# Embedded_Circuits.net
KiCad netlist of a schematic drawn in Altium Designer
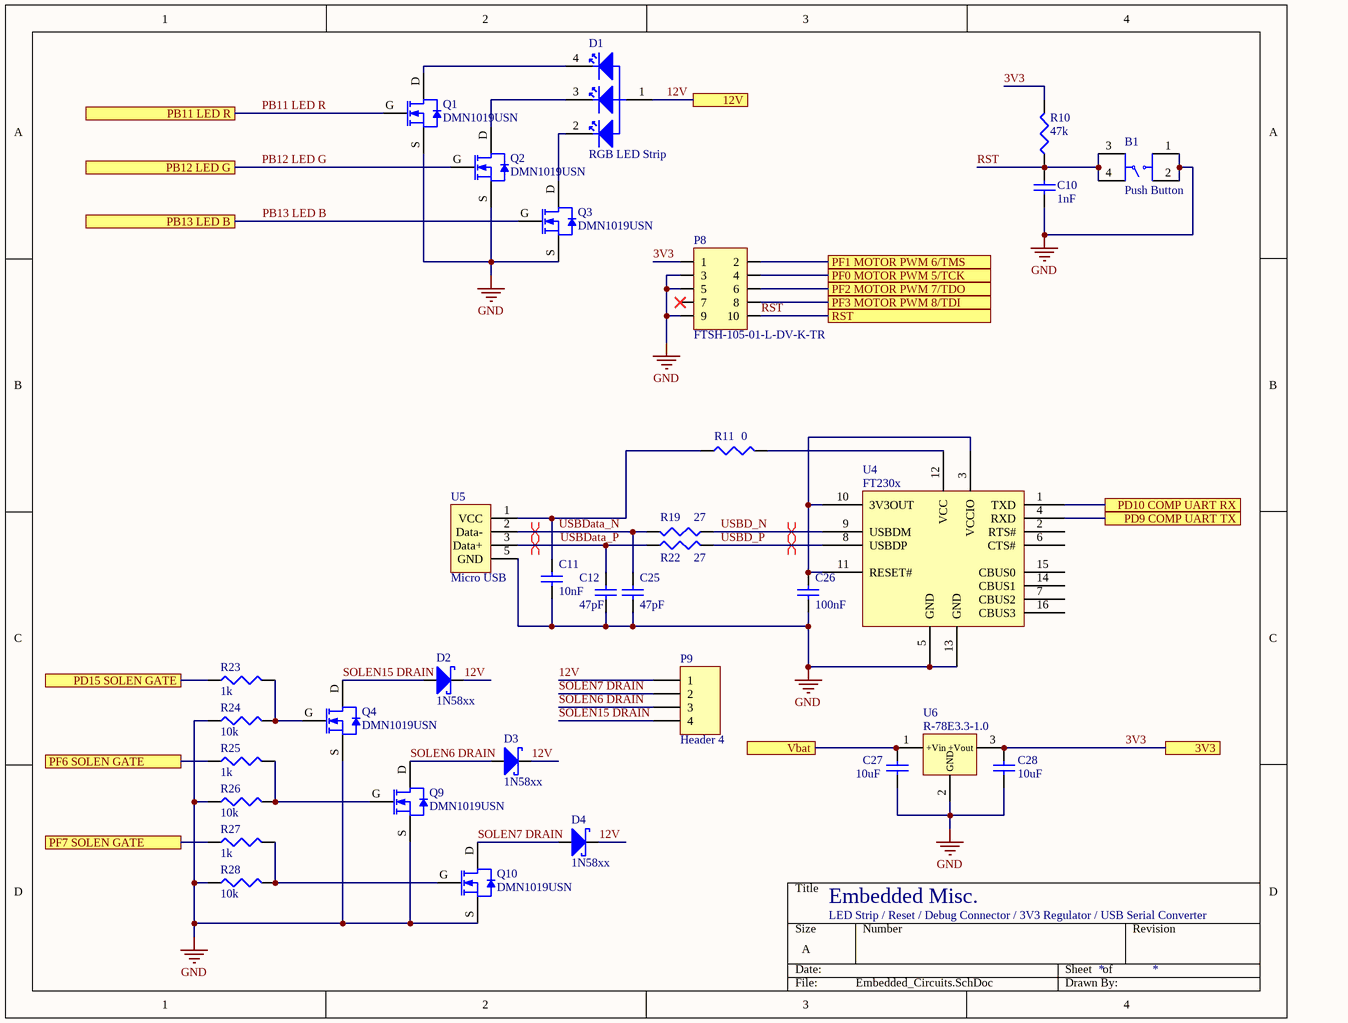
[diagram p0: Embedded_Circuits.SchDoc]

(export (version "E")
  (design (tool "Eeschema 10.0.6"))
  (components
    (comp (ref "B1")
      (value "Push Button")
      (footprint "Push Button")
      (description "Tactile Switch SPST-NO Top Actuated Through Hole")
      (libsource (lib "Power_Embedded_Board_Library") (part "Push Button"))
    )
    (comp (ref "C10")
      (value "1nF")
      (footprint "C1206")
      (description "Capacitor (Semiconductor SIM Model)")
      (fields (field (name "Comment") "Cap Semi") (field (name "PUBLISHER") "Altium Limited"))
      (libsource (lib "Miscellaneous Devices") (part "Cap Semi"))
    )
    (comp (ref "C11")
      (value "10nF")
      (footprint "C1206")
      (description "Capacitor")
      (fields (field (name "Comment") "Cap") (field (name "PUBLISHER") "Altium Limited"))
      (libsource (lib "Miscellaneous Devices") (part "Cap"))
    )
    (comp (ref "C12")
      (value "47pF")
      (footprint "C1206")
      (description "Capacitor")
      (fields (field (name "Comment") "Cap") (field (name "PUBLISHER") "Altium Limited"))
      (libsource (lib "Miscellaneous Devices") (part "Cap"))
    )
    (comp (ref "C25")
      (value "47pF")
      (footprint "C1206")
      (description "Capacitor")
      (fields (field (name "Comment") "Cap") (field (name "PUBLISHER") "Altium Limited"))
      (libsource (lib "Miscellaneous Devices") (part "Cap"))
    )
    (comp (ref "C26")
      (value "100nF")
      (footprint "C1206")
      (description "Capacitor")
      (fields (field (name "Comment") "Cap") (field (name "PUBLISHER") "Altium Limited"))
      (libsource (lib "Miscellaneous Devices") (part "Cap"))
    )
    (comp (ref "C27")
      (value "10uF")
      (footprint "C1206")
      (description "Capacitor")
      (fields (field (name "Comment") "Cap") (field (name "PUBLISHER") "Altium Limited"))
      (libsource (lib "Miscellaneous Devices") (part "Cap"))
    )
    (comp (ref "C28")
      (value "10uF")
      (footprint "C1206")
      (description "Capacitor")
      (fields (field (name "Comment") "Cap") (field (name "PUBLISHER") "Altium Limited"))
      (libsource (lib "Miscellaneous Devices") (part "Cap"))
    )
    (comp (ref "D1")
      (value "RGB LED Strip")
      (footprint "Header 1x4")
      (description "LED RGB Strip - Bare Nonaddressable")
      (libsource (lib "Power_Embedded_Board_Library") (part "RGB LED Strip"))
    )
    (comp (ref "D2")
      (value "1N58xx")
      (footprint "1N58xx")
      (description "1A Schottky Barrier Rectifier Diode")
      (libsource (lib "Power_Embedded_Board_Library") (part "1N58xx"))
    )
    (comp (ref "D3")
      (value "1N58xx")
      (footprint "1N58xx")
      (description "1A Schottky Barrier Rectifier Diode")
      (libsource (lib "Power_Embedded_Board_Library") (part "1N58xx"))
    )
    (comp (ref "D4")
      (value "1N58xx")
      (footprint "1N58xx")
      (description "1A Schottky Barrier Rectifier Diode")
      (libsource (lib "Power_Embedded_Board_Library") (part "1N58xx"))
    )
    (comp (ref "P8")
      (value "FTSH-105-01-L-DV-K-TR")
      (footprint "FTSH-105-01-L-DV-K-TR")
      (description "CONN HEADER 10POS DUAL .05\" SMD")
      (libsource (lib "Power_Embedded_Board_Library") (part "JTAG Header"))
    )
    (comp (ref "P9")
      (value "Header 4")
      (footprint "Header 1x4")
      (description "Header, 4-Pin")
      (fields (field (name "PUBLISHER") "Altium Limited"))
      (libsource (lib "Miscellaneous Connectors") (part "Header 4"))
    )
    (comp (ref "Q1")
      (value "DMN1019USN")
      (footprint "SOT-23")
      (description "12V N-Channel Enhancement Mode MOSFET")
      (libsource (lib "Power_Embedded_Board_Library") (part "DMN1019USN"))
    )
    (comp (ref "Q2")
      (value "DMN1019USN")
      (footprint "SOT-23")
      (description "12V N-Channel Enhancement Mode MOSFET")
      (libsource (lib "Power_Embedded_Board_Library") (part "DMN1019USN"))
    )
    (comp (ref "Q3")
      (value "DMN1019USN")
      (footprint "SOT-23")
      (description "12V N-Channel Enhancement Mode MOSFET")
      (libsource (lib "Power_Embedded_Board_Library") (part "DMN1019USN"))
    )
    (comp (ref "Q4")
      (value "DMN1019USN")
      (footprint "SOT-23")
      (description "12V N-Channel Enhancement Mode MOSFET")
      (libsource (lib "Power_Embedded_Board_Library") (part "DMN1019USN"))
    )
    (comp (ref "Q9")
      (value "DMN1019USN")
      (footprint "SOT-23")
      (description "12V N-Channel Enhancement Mode MOSFET")
      (libsource (lib "Power_Embedded_Board_Library") (part "DMN1019USN"))
    )
    (comp (ref "Q10")
      (value "DMN1019USN")
      (footprint "SOT-23")
      (description "12V N-Channel Enhancement Mode MOSFET")
      (libsource (lib "Power_Embedded_Board_Library") (part "DMN1019USN"))
    )
    (comp (ref "R10")
      (value "47k")
      (footprint "J1-0603")
      (description "Resistor")
      (fields (field (name "Comment") "Res3") (field (name "PUBLISHER") "Altium Limited"))
      (libsource (lib "Miscellaneous Devices") (part "Res3"))
    )
    (comp (ref "R11")
      (value "0")
      (footprint "J1-0603")
      (description "Resistor")
      (fields (field (name "Comment") "Res3") (field (name "PUBLISHER") "Altium Limited"))
      (libsource (lib "Miscellaneous Devices") (part "Res3"))
    )
    (comp (ref "R19")
      (value "27")
      (footprint "J1-0603")
      (description "Resistor")
      (fields (field (name "Comment") "Res3") (field (name "PUBLISHER") "Altium Limited"))
      (libsource (lib "Miscellaneous Devices") (part "Res3"))
    )
    (comp (ref "R22")
      (value "27")
      (footprint "J1-0603")
      (description "Resistor")
      (fields (field (name "Comment") "Res3") (field (name "PUBLISHER") "Altium Limited"))
      (libsource (lib "Miscellaneous Devices") (part "Res3"))
    )
    (comp (ref "R23")
      (value "1k")
      (footprint "J1-0603")
      (description "Resistor")
      (fields (field (name "Comment") "Res3") (field (name "PUBLISHER") "Altium Limited"))
      (libsource (lib "Miscellaneous Devices") (part "Res3"))
    )
    (comp (ref "R24")
      (value "10k")
      (footprint "J1-0603")
      (description "Resistor")
      (fields (field (name "Comment") "Res3") (field (name "PUBLISHER") "Altium Limited"))
      (libsource (lib "Miscellaneous Devices") (part "Res3"))
    )
    (comp (ref "R25")
      (value "1k")
      (footprint "J1-0603")
      (description "Resistor")
      (fields (field (name "Comment") "Res3") (field (name "PUBLISHER") "Altium Limited"))
      (libsource (lib "Miscellaneous Devices") (part "Res3"))
    )
    (comp (ref "R26")
      (value "10k")
      (footprint "J1-0603")
      (description "Resistor")
      (fields (field (name "Comment") "Res3") (field (name "PUBLISHER") "Altium Limited"))
      (libsource (lib "Miscellaneous Devices") (part "Res3"))
    )
    (comp (ref "R27")
      (value "1k")
      (footprint "J1-0603")
      (description "Resistor")
      (fields (field (name "Comment") "Res3") (field (name "PUBLISHER") "Altium Limited"))
      (libsource (lib "Miscellaneous Devices") (part "Res3"))
    )
    (comp (ref "R28")
      (value "10k")
      (footprint "J1-0603")
      (description "Resistor")
      (fields (field (name "Comment") "Res3") (field (name "PUBLISHER") "Altium Limited"))
      (libsource (lib "Miscellaneous Devices") (part "Res3"))
    )
    (comp (ref "U4")
      (value "FT230x")
      (footprint "FT230X")
      (description "USB to Basic UART IC")
      (libsource (lib "Power_Embedded_Board_Library") (part "FTDI FT230x"))
    )
    (comp (ref "U5")
      (value "Micro USB")
      (footprint "Micro USB")
      (description "USB - micro B USB 2.0 Receptacle Connector 5 Position Surface Mount, Right Angle")
      (libsource (lib "Power_Embedded_Board_Library") (part "Micro USB"))
    )
    (comp (ref "U6")
      (value "R-78E3.3-1.0")
      (footprint "R-78Exx-1.0")
      (description "1A DC/DC Voltage Converter")
      (libsource (lib "Power_Embedded_Board_Library") (part "R-78Exx-1.0"))
    )
  )
  (nets
    (net (code "1") (name "/3V3") (class "Default")
      (node (ref "C28") (pin "2") (pinfunction "2_2") (pintype "passive"))
      (node (ref "P8") (pin "1") (pinfunction "1_1") (pintype "passive"))
      (node (ref "R10") (pin "2") (pinfunction "2_2") (pintype "passive"))
      (node (ref "U6") (pin "3") (pinfunction "+Vout_3") (pintype "passive"))
    )
    (net (code "2") (name "/12V") (class "Default")
      (node (ref "D1") (pin "1") (pinfunction "1_1") (pintype "passive"))
      (node (ref "D2") (pin "K") (pinfunction "Cathode_K") (pintype "passive"))
      (node (ref "D3") (pin "K") (pinfunction "Cathode_K") (pintype "passive"))
      (node (ref "D4") (pin "K") (pinfunction "Cathode_K") (pintype "passive"))
      (node (ref "P9") (pin "1") (pinfunction "1_1") (pintype "passive"))
    )
    (net (code "3") (name "/PB11 LED R") (class "Default")
      (node (ref "Q1") (pin "G") (pinfunction "G_G") (pintype "passive"))
    )
    (net (code "4") (name "/PB12 LED G") (class "Default")
      (node (ref "Q2") (pin "G") (pinfunction "G_G") (pintype "passive"))
    )
    (net (code "5") (name "/PB13 LED B") (class "Default")
      (node (ref "Q3") (pin "G") (pinfunction "G_G") (pintype "passive"))
    )
    (net (code "6") (name "/PD9 COMP UART TX") (class "Default")
      (node (ref "U4") (pin "4") (pinfunction "RXD_4") (pintype "passive"))
    )
    (net (code "7") (name "/PD10 COMP UART RX") (class "Default")
      (node (ref "U4") (pin "1") (pinfunction "TXD_1") (pintype "passive"))
    )
    (net (code "8") (name "/PD15 SOLEN GATE") (class "Default")
      (node (ref "R23") (pin "1") (pinfunction "1_1") (pintype "passive"))
    )
    (net (code "9") (name "/PF0 MOTOR PWM 5{slash}TCK") (class "Default")
      (node (ref "P8") (pin "4") (pinfunction "4_4") (pintype "passive"))
    )
    (net (code "10") (name "/PF1 MOTOR PWM 6{slash}TMS") (class "Default")
      (node (ref "P8") (pin "2") (pinfunction "2_2") (pintype "passive"))
    )
    (net (code "11") (name "/PF2 MOTOR PWM 7{slash}TDO") (class "Default")
      (node (ref "P8") (pin "6") (pinfunction "6_6") (pintype "passive"))
    )
    (net (code "12") (name "/PF3 MOTOR PWM 8{slash}TDI") (class "Default")
      (node (ref "P8") (pin "8") (pinfunction "8_8") (pintype "passive"))
    )
    (net (code "13") (name "/PF6 SOLEN GATE") (class "Default")
      (node (ref "R25") (pin "1") (pinfunction "1_1") (pintype "passive"))
    )
    (net (code "14") (name "/PF7 SOLEN GATE") (class "Default")
      (node (ref "R27") (pin "1") (pinfunction "1_1") (pintype "passive"))
    )
    (net (code "15") (name "/RST") (class "Default")
      (node (ref "B1") (pin "3") (pinfunction "3_3") (pintype "passive"))
      (node (ref "B1") (pin "4") (pinfunction "4_4") (pintype "passive"))
      (node (ref "C10") (pin "2") (pinfunction "2_2") (pintype "passive"))
      (node (ref "P8") (pin "10") (pinfunction "10_10") (pintype "passive"))
      (node (ref "R10") (pin "1") (pinfunction "1_1") (pintype "passive"))
    )
    (net (code "16") (name "/SOLEN6 DRAIN") (class "Default")
      (node (ref "D3") (pin "A") (pinfunction "Anode_A") (pintype "passive"))
      (node (ref "P9") (pin "3") (pinfunction "3_3") (pintype "passive"))
      (node (ref "Q9") (pin "D") (pinfunction "D_D") (pintype "passive"))
    )
    (net (code "17") (name "/SOLEN7 DRAIN") (class "Default")
      (node (ref "D4") (pin "A") (pinfunction "Anode_A") (pintype "passive"))
      (node (ref "P9") (pin "2") (pinfunction "2_2") (pintype "passive"))
      (node (ref "Q10") (pin "D") (pinfunction "D_D") (pintype "passive"))
    )
    (net (code "18") (name "/SOLEN15 DRAIN") (class "Default")
      (node (ref "D2") (pin "A") (pinfunction "Anode_A") (pintype "passive"))
      (node (ref "P9") (pin "4") (pinfunction "4_4") (pintype "passive"))
      (node (ref "Q4") (pin "D") (pinfunction "D_D") (pintype "passive"))
    )
    (net (code "19") (name "/USBD_N") (class "Default")
      (node (ref "R19") (pin "1") (pinfunction "1_1") (pintype "passive"))
      (node (ref "U4") (pin "9") (pinfunction "USBDM_9") (pintype "passive"))
    )
    (net (code "20") (name "/USBD_P") (class "Default")
      (node (ref "R22") (pin "2") (pinfunction "2_2") (pintype "passive"))
      (node (ref "U4") (pin "8") (pinfunction "USBDP_8") (pintype "passive"))
    )
    (net (code "21") (name "/USBData_N") (class "Default")
      (node (ref "C25") (pin "2") (pinfunction "2_2") (pintype "passive"))
      (node (ref "R19") (pin "2") (pinfunction "2_2") (pintype "passive"))
      (node (ref "U5") (pin "2") (pinfunction "Data-_2") (pintype "passive"))
    )
    (net (code "22") (name "/USBData_P") (class "Default")
      (node (ref "C12") (pin "2") (pinfunction "2_2") (pintype "passive"))
      (node (ref "R22") (pin "1") (pinfunction "1_1") (pintype "passive"))
      (node (ref "U5") (pin "3") (pinfunction "Data+_3") (pintype "passive"))
    )
    (net (code "23") (name "/Vbat") (class "Default")
      (node (ref "C27") (pin "2") (pinfunction "2_2") (pintype "passive"))
      (node (ref "U6") (pin "1") (pinfunction "+Vin_1") (pintype "passive"))
    )
    (net (code "24") (name "GND") (class "Default")
      (node (ref "B1") (pin "1") (pinfunction "1_1") (pintype "passive"))
      (node (ref "B1") (pin "2") (pinfunction "2_2") (pintype "passive"))
      (node (ref "C10") (pin "1") (pinfunction "1_1") (pintype "passive"))
      (node (ref "C11") (pin "1") (pinfunction "1_1") (pintype "passive"))
      (node (ref "C12") (pin "1") (pinfunction "1_1") (pintype "passive"))
      (node (ref "C25") (pin "1") (pinfunction "1_1") (pintype "passive"))
      (node (ref "C26") (pin "1") (pinfunction "1_1") (pintype "passive"))
      (node (ref "C27") (pin "1") (pinfunction "1_1") (pintype "passive"))
      (node (ref "C28") (pin "1") (pinfunction "1_1") (pintype "passive"))
      (node (ref "P8") (pin "3") (pinfunction "3_3") (pintype "passive"))
      (node (ref "P8") (pin "5") (pinfunction "5_5") (pintype "passive"))
      (node (ref "P8") (pin "9") (pinfunction "9_9") (pintype "passive"))
      (node (ref "Q1") (pin "S") (pinfunction "S_S") (pintype "passive"))
      (node (ref "Q10") (pin "S") (pinfunction "S_S") (pintype "passive"))
      (node (ref "Q2") (pin "S") (pinfunction "S_S") (pintype "passive"))
      (node (ref "Q3") (pin "S") (pinfunction "S_S") (pintype "passive"))
      (node (ref "Q4") (pin "S") (pinfunction "S_S") (pintype "passive"))
      (node (ref "Q9") (pin "S") (pinfunction "S_S") (pintype "passive"))
      (node (ref "R24") (pin "1") (pinfunction "1_1") (pintype "passive"))
      (node (ref "R26") (pin "1") (pinfunction "1_1") (pintype "passive"))
      (node (ref "R28") (pin "1") (pinfunction "1_1") (pintype "passive"))
      (node (ref "U4") (pin "13") (pinfunction "GND_13") (pintype "passive"))
      (node (ref "U4") (pin "5") (pinfunction "GND_5") (pintype "passive"))
      (node (ref "U5") (pin "5") (pinfunction "GND_5") (pintype "passive"))
      (node (ref "U6") (pin "2") (pinfunction "GND_2") (pintype "passive"))
    )
    (net (code "25") (name "Net-(D1-Pad2)") (class "Default")
      (node (ref "D1") (pin "2") (pinfunction "2_2") (pintype "passive"))
      (node (ref "Q3") (pin "D") (pinfunction "D_D") (pintype "passive"))
    )
    (net (code "26") (name "Net-(D1-Pad3)") (class "Default")
      (node (ref "D1") (pin "3") (pinfunction "3_3") (pintype "passive"))
      (node (ref "Q2") (pin "D") (pinfunction "D_D") (pintype "passive"))
    )
    (net (code "27") (name "Net-(D1-Pad4)") (class "Default")
      (node (ref "D1") (pin "4") (pinfunction "4_4") (pintype "passive"))
      (node (ref "Q1") (pin "D") (pinfunction "D_D") (pintype "passive"))
    )
    (net (code "28") (name "Net-(Q4-PadG)") (class "Default")
      (node (ref "Q4") (pin "G") (pinfunction "G_G") (pintype "passive"))
      (node (ref "R23") (pin "2") (pinfunction "2_2") (pintype "passive"))
      (node (ref "R24") (pin "2") (pinfunction "2_2") (pintype "passive"))
    )
    (net (code "29") (name "Net-(Q9-PadG)") (class "Default")
      (node (ref "Q9") (pin "G") (pinfunction "G_G") (pintype "passive"))
      (node (ref "R25") (pin "2") (pinfunction "2_2") (pintype "passive"))
      (node (ref "R26") (pin "2") (pinfunction "2_2") (pintype "passive"))
    )
    (net (code "30") (name "Net-(Q10-PadG)") (class "Default")
      (node (ref "Q10") (pin "G") (pinfunction "G_G") (pintype "passive"))
      (node (ref "R27") (pin "2") (pinfunction "2_2") (pintype "passive"))
      (node (ref "R28") (pin "2") (pinfunction "2_2") (pintype "passive"))
    )
    (net (code "31") (name "Net-(U4-3V3OUT)") (class "Default")
      (node (ref "C26") (pin "2") (pinfunction "2_2") (pintype "passive"))
      (node (ref "U4") (pin "10") (pinfunction "3V3OUT_10") (pintype "passive"))
      (node (ref "U4") (pin "11") (pinfunction "RESET#_11") (pintype "passive"))
      (node (ref "U4") (pin "3") (pinfunction "VCCIO_3") (pintype "passive"))
    )
    (net (code "32") (name "Net-(U4-VCC)") (class "Default")
      (node (ref "R11") (pin "2") (pinfunction "2_2") (pintype "passive"))
      (node (ref "U4") (pin "12") (pinfunction "VCC_12") (pintype "passive"))
    )
    (net (code "33") (name "Net-(U5-VCC)") (class "Default")
      (node (ref "C11") (pin "2") (pinfunction "2_2") (pintype "passive"))
      (node (ref "R11") (pin "1") (pinfunction "1_1") (pintype "passive"))
      (node (ref "U5") (pin "1") (pinfunction "VCC_1") (pintype "passive"))
    )
    (net (code "34") (name "unconnected-(P8-Pad7)") (class "Default")
      (node (ref "P8") (pin "7") (pinfunction "7_7") (pintype "passive+no_connect"))
    )
    (net (code "35") (name "unconnected-(U4-CBUS0-Pad15)") (class "Default")
      (node (ref "U4") (pin "15") (pinfunction "CBUS0_15") (pintype "passive"))
    )
    (net (code "36") (name "unconnected-(U4-CBUS1-Pad14)") (class "Default")
      (node (ref "U4") (pin "14") (pinfunction "CBUS1_14") (pintype "passive"))
    )
    (net (code "37") (name "unconnected-(U4-CBUS2-Pad7)") (class "Default")
      (node (ref "U4") (pin "7") (pinfunction "CBUS2_7") (pintype "passive"))
    )
    (net (code "38") (name "unconnected-(U4-CBUS3-Pad16)") (class "Default")
      (node (ref "U4") (pin "16") (pinfunction "CBUS3_16") (pintype "passive"))
    )
    (net (code "39") (name "unconnected-(U4-CTS#-Pad6)") (class "Default")
      (node (ref "U4") (pin "6") (pinfunction "CTS#_6") (pintype "passive"))
    )
    (net (code "40") (name "unconnected-(U4-RTS#-Pad2)") (class "Default")
      (node (ref "U4") (pin "2") (pinfunction "RTS#_2") (pintype "passive"))
    )
  )
)
